# Sheet1.net
KiCad netlist of a schematic drawn in Altium Designer
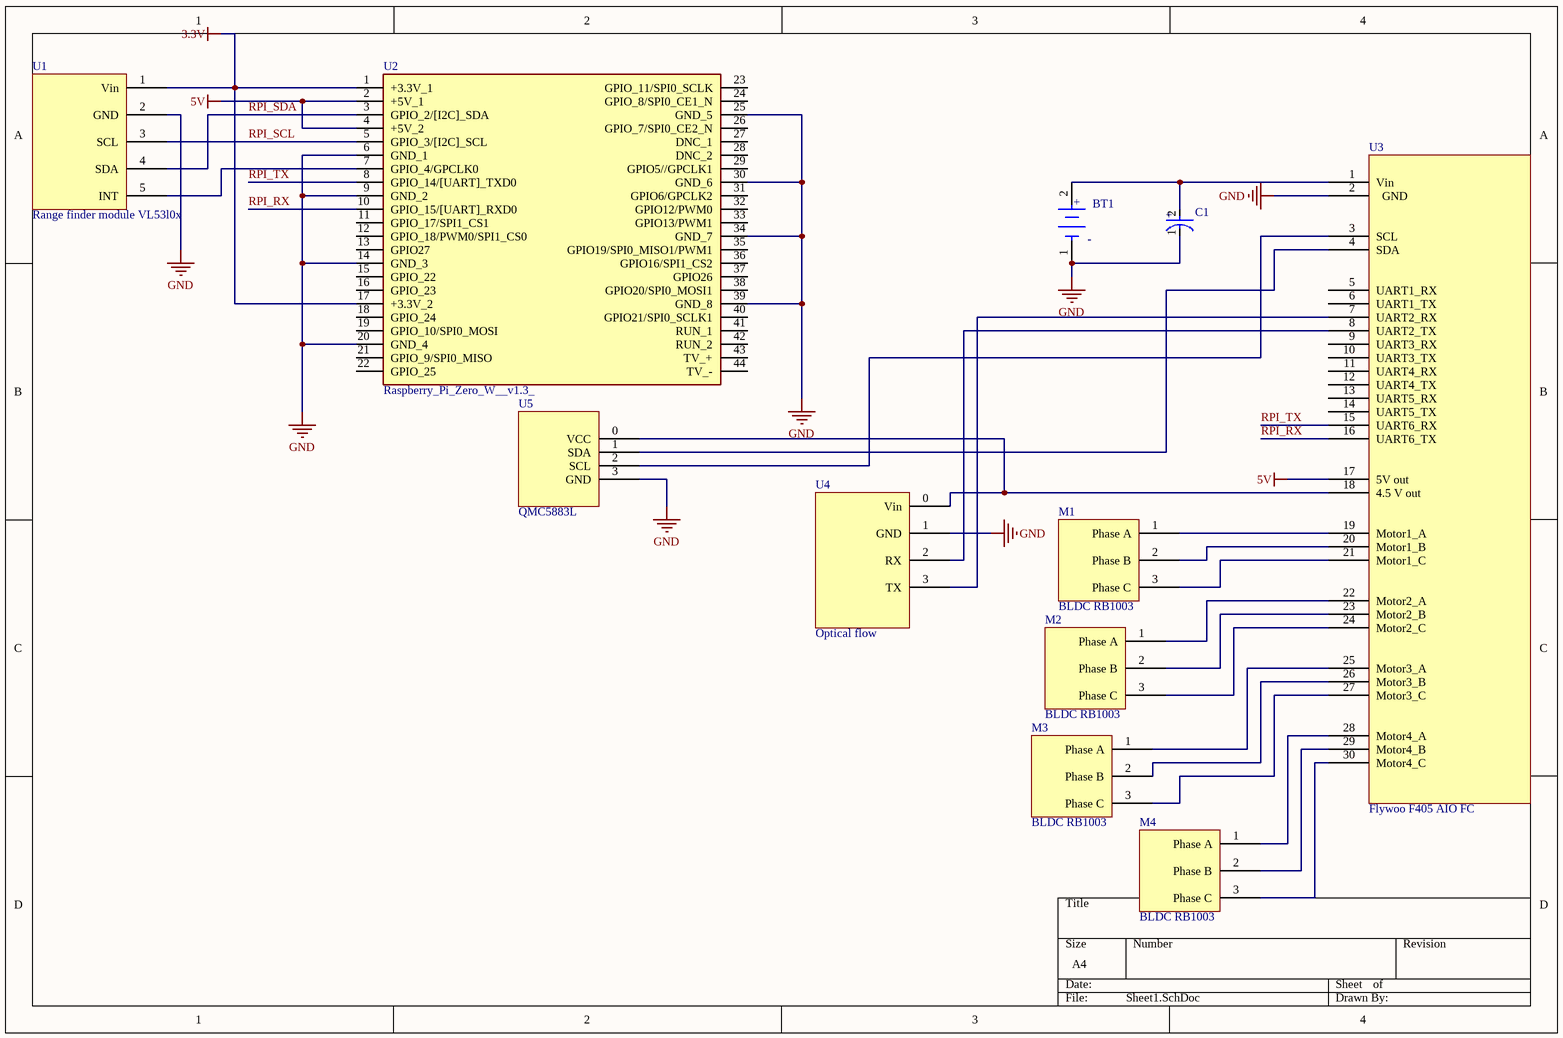
[diagram p0: Sheet1.SchDoc]

(export (version "E")
  (design (tool "Eeschema 10.0.6"))
  (components
    (comp (ref "BT1")
      (value "S8411-45R")
      (footprint "FP-S8411-45R-MFG")
      (description "BATTERY HOLDER COIN 12MM SMD")
      (libsource (lib "Altium Content Vault") (part "60d3b5b901a8747834971d0eb8cf3fd"))
    )
    (comp (ref "C1")
      (value "EEEFK1H101P")
      (footprint "FP-FKF-MFG")
      (description "CAP ALUM 100UF 20% 50V SMD")
      (fields (field (name "VOLTAGE") "50V") (field (name "TOLERANCE") "20%"))
      (libsource (lib "Altium Content Vault") (part "a00bbbee19879c290e62620ae7e47b1"))
    )
    (comp (ref "M1") (value "BLDC RB1003") (libsource (lib "Schlib1") (part "BLDC RB1003")))
    (comp (ref "M2") (value "BLDC RB1003") (libsource (lib "Schlib1") (part "BLDC RB1003")))
    (comp (ref "M3") (value "BLDC RB1003") (libsource (lib "Schlib1") (part "BLDC RB1003")))
    (comp (ref "M4") (value "BLDC RB1003") (libsource (lib "Schlib1") (part "BLDC RB1003")))
    (comp (ref "U1")
      (value "Range finder module VL53l0x")
      (libsource (lib "Schlib1") (part "Range finder module VL53l0x"))
    )
    (comp (ref "U2")
      (value "Raspberry_Pi_Zero_W__v1.3_")
      (footprint "SamacSys:RASPBERRYPIZEROWV13")
      (description "Integrated Circuit")
      (fields (field (name "MANUFACTURER_PART_NUMBER") "Raspberry Pi Zero W (v1.3)"))
      (libsource (lib "*") (part "Raspberry_Pi_Zero_W__v1.3_"))
    )
    (comp (ref "U3") (value "Flywoo F405 AIO FC") (libsource (lib "Schlib1") (part "Flywoo F405 AIO FC")))
    (comp (ref "U4") (value "Optical flow") (libsource (lib "Schlib1") (part "MTF_02 (PMW3901)")))
    (comp (ref "U5") (value "QMC5883L") (libsource (lib "Schlib1") (part "QMC5883L")))
  )
  (nets
    (net (code "1") (name "/RPI_RX") (class "Default")
      (node (ref "U2") (pin "10") (pinfunction "GPIO_15/[UART]_RXD0_10") (pintype "passive"))
      (node (ref "U3") (pin "16") (pinfunction "UART6_TX_16") (pintype "passive"))
    )
    (net (code "2") (name "/RPI_SCL") (class "Default")
      (node (ref "U1") (pin "3") (pinfunction "SCL_3") (pintype "passive"))
      (node (ref "U2") (pin "5") (pinfunction "GPIO_3/[I2C]_SCL_5") (pintype "passive"))
    )
    (net (code "3") (name "/RPI_SDA") (class "Default")
      (node (ref "U1") (pin "4") (pinfunction "SDA_4") (pintype "passive"))
      (node (ref "U2") (pin "3") (pinfunction "GPIO_2/[I2C]_SDA_3") (pintype "passive"))
    )
    (net (code "4") (name "/RPI_TX") (class "Default")
      (node (ref "U2") (pin "8") (pinfunction "GPIO_14/[UART]_TXD0_8") (pintype "passive"))
      (node (ref "U3") (pin "15") (pinfunction "UART6_RX_15") (pintype "passive"))
    )
    (net (code "5") (name "3.3V") (class "Default")
      (node (ref "U1") (pin "1") (pinfunction "Vin_1") (pintype "passive"))
      (node (ref "U2") (pin "1") (pinfunction "+3.3V_1_1") (pintype "passive"))
      (node (ref "U2") (pin "17") (pinfunction "+3.3V_2_17") (pintype "passive"))
    )
    (net (code "6") (name "5V") (class "Default")
      (node (ref "U2") (pin "2") (pinfunction "+5V_1_2") (pintype "passive"))
      (node (ref "U2") (pin "4") (pinfunction "+5V_2_4") (pintype "passive"))
      (node (ref "U3") (pin "17") (pinfunction "5V_out_17") (pintype "passive"))
    )
    (net (code "7") (name "GND") (class "Default")
      (node (ref "BT1") (pin "1") (pinfunction "C_1") (pintype "passive"))
      (node (ref "C1") (pin "1") (pinfunction "C_1") (pintype "passive"))
      (node (ref "U1") (pin "2") (pinfunction "GND_2") (pintype "passive"))
      (node (ref "U2") (pin "14") (pinfunction "GND_3_14") (pintype "passive"))
      (node (ref "U2") (pin "20") (pinfunction "GND_4_20") (pintype "passive"))
      (node (ref "U2") (pin "25") (pinfunction "GND_5_25") (pintype "passive"))
      (node (ref "U2") (pin "30") (pinfunction "GND_6_30") (pintype "passive"))
      (node (ref "U2") (pin "34") (pinfunction "GND_7_34") (pintype "passive"))
      (node (ref "U2") (pin "39") (pinfunction "GND_8_39") (pintype "passive"))
      (node (ref "U2") (pin "6") (pinfunction "GND_1_6") (pintype "passive"))
      (node (ref "U2") (pin "9") (pinfunction "GND_2_9") (pintype "passive"))
      (node (ref "U3") (pin "2") (pinfunction "__GND_2") (pintype "passive"))
      (node (ref "U4") (pin "1") (pinfunction "GND_1") (pintype "passive"))
      (node (ref "U5") (pin "3") (pinfunction "GND_3") (pintype "passive"))
    )
    (net (code "8") (name "Net-(BT1-A)") (class "Default")
      (node (ref "BT1") (pin "2") (pinfunction "A_2") (pintype "passive"))
      (node (ref "C1") (pin "2") (pinfunction "A_2") (pintype "passive"))
      (node (ref "U3") (pin "1") (pinfunction "Vin_1") (pintype "passive"))
    )
    (net (code "9") (name "Net-(M1-Phase_A)") (class "Default")
      (node (ref "M1") (pin "1") (pinfunction "Phase_A_1") (pintype "passive"))
      (node (ref "U3") (pin "19") (pinfunction "Motor1_A_19") (pintype "passive"))
    )
    (net (code "10") (name "Net-(M1-Phase_B)") (class "Default")
      (node (ref "M1") (pin "2") (pinfunction "Phase_B_2") (pintype "passive"))
      (node (ref "U3") (pin "20") (pinfunction "Motor1_B_20") (pintype "passive"))
    )
    (net (code "11") (name "Net-(M1-Phase_C)") (class "Default")
      (node (ref "M1") (pin "3") (pinfunction "Phase_C_3") (pintype "passive"))
      (node (ref "U3") (pin "21") (pinfunction "Motor1_C_21") (pintype "passive"))
    )
    (net (code "12") (name "Net-(M2-Phase_A)") (class "Default")
      (node (ref "M2") (pin "1") (pinfunction "Phase_A_1") (pintype "passive"))
      (node (ref "U3") (pin "22") (pinfunction "Motor2_A_22") (pintype "passive"))
    )
    (net (code "13") (name "Net-(M2-Phase_B)") (class "Default")
      (node (ref "M2") (pin "2") (pinfunction "Phase_B_2") (pintype "passive"))
      (node (ref "U3") (pin "23") (pinfunction "Motor2_B_23") (pintype "passive"))
    )
    (net (code "14") (name "Net-(M2-Phase_C)") (class "Default")
      (node (ref "M2") (pin "3") (pinfunction "Phase_C_3") (pintype "passive"))
      (node (ref "U3") (pin "24") (pinfunction "Motor2_C_24") (pintype "passive"))
    )
    (net (code "15") (name "Net-(M3-Phase_A)") (class "Default")
      (node (ref "M3") (pin "1") (pinfunction "Phase_A_1") (pintype "passive"))
      (node (ref "U3") (pin "25") (pinfunction "Motor3_A_25") (pintype "passive"))
    )
    (net (code "16") (name "Net-(M3-Phase_B)") (class "Default")
      (node (ref "M3") (pin "2") (pinfunction "Phase_B_2") (pintype "passive"))
      (node (ref "U3") (pin "26") (pinfunction "Motor3_B_26") (pintype "passive"))
    )
    (net (code "17") (name "Net-(M3-Phase_C)") (class "Default")
      (node (ref "M3") (pin "3") (pinfunction "Phase_C_3") (pintype "passive"))
      (node (ref "U3") (pin "27") (pinfunction "Motor3_C_27") (pintype "passive"))
    )
    (net (code "18") (name "Net-(M4-Phase_A)") (class "Default")
      (node (ref "M4") (pin "1") (pinfunction "Phase_A_1") (pintype "passive"))
      (node (ref "U3") (pin "28") (pinfunction "Motor4_A_28") (pintype "passive"))
    )
    (net (code "19") (name "Net-(M4-Phase_B)") (class "Default")
      (node (ref "M4") (pin "2") (pinfunction "Phase_B_2") (pintype "passive"))
      (node (ref "U3") (pin "29") (pinfunction "Motor4_B_29") (pintype "passive"))
    )
    (net (code "20") (name "Net-(M4-Phase_C)") (class "Default")
      (node (ref "M4") (pin "3") (pinfunction "Phase_C_3") (pintype "passive"))
      (node (ref "U3") (pin "30") (pinfunction "Motor4_C_30") (pintype "passive"))
    )
    (net (code "21") (name "Net-(U1-INT)") (class "Default")
      (node (ref "U1") (pin "5") (pinfunction "INT_5") (pintype "passive"))
      (node (ref "U2") (pin "7") (pinfunction "GPIO_4/GPCLK0_7") (pintype "passive"))
    )
    (net (code "22") (name "Net-(U3-4.5_V_out)") (class "Default")
      (node (ref "U3") (pin "18") (pinfunction "4.5_V_out_18") (pintype "passive"))
      (node (ref "U4") (pin "0") (pinfunction "Vin_0") (pintype "passive"))
      (node (ref "U5") (pin "0") (pinfunction "VCC_0") (pintype "passive"))
    )
    (net (code "23") (name "Net-(U3-SCL)") (class "Default")
      (node (ref "U3") (pin "3") (pinfunction "SCL_3") (pintype "passive"))
      (node (ref "U5") (pin "2") (pinfunction "SCL_2") (pintype "passive"))
    )
    (net (code "24") (name "Net-(U3-SDA)") (class "Default")
      (node (ref "U3") (pin "4") (pinfunction "SDA_4") (pintype "passive"))
      (node (ref "U5") (pin "1") (pinfunction "SDA_1") (pintype "passive"))
    )
    (net (code "25") (name "Net-(U3-UART2_RX)") (class "Default")
      (node (ref "U3") (pin "7") (pinfunction "UART2_RX_7") (pintype "passive"))
      (node (ref "U4") (pin "3") (pinfunction "TX_3") (pintype "passive"))
    )
    (net (code "26") (name "Net-(U3-UART2_TX)") (class "Default")
      (node (ref "U3") (pin "8") (pinfunction "UART2_TX_8") (pintype "passive"))
      (node (ref "U4") (pin "2") (pinfunction "RX_2") (pintype "passive"))
    )
    (net (code "27") (name "unconnected-(U2-DNC_1-Pad27)") (class "Default")
      (node (ref "U2") (pin "27") (pinfunction "DNC_1_27") (pintype "passive"))
    )
    (net (code "28") (name "unconnected-(U2-DNC_2-Pad28)") (class "Default")
      (node (ref "U2") (pin "28") (pinfunction "DNC_2_28") (pintype "passive"))
    )
    (net (code "29") (name "unconnected-(U2-GPIO5{slash}{slash}GPCLK1-Pad29)") (class "Default")
      (node (ref "U2") (pin "29") (pinfunction "GPIO5//GPCLK1_29") (pintype "passive"))
    )
    (net (code "30") (name "unconnected-(U2-GPIO6{slash}GPCLK2-Pad31)") (class "Default")
      (node (ref "U2") (pin "31") (pinfunction "GPIO6/GPCLK2_31") (pintype "passive"))
    )
    (net (code "31") (name "unconnected-(U2-GPIO12{slash}PWM0-Pad32)") (class "Default")
      (node (ref "U2") (pin "32") (pinfunction "GPIO12/PWM0_32") (pintype "passive"))
    )
    (net (code "32") (name "unconnected-(U2-GPIO13{slash}PWM1-Pad33)") (class "Default")
      (node (ref "U2") (pin "33") (pinfunction "GPIO13/PWM1_33") (pintype "passive"))
    )
    (net (code "33") (name "unconnected-(U2-GPIO16{slash}SPI1_CS2-Pad36)") (class "Default")
      (node (ref "U2") (pin "36") (pinfunction "GPIO16/SPI1_CS2_36") (pintype "passive"))
    )
    (net (code "34") (name "unconnected-(U2-GPIO19{slash}SPI0_MISO1{slash}PWM1-Pad35)") (class "Default")
      (node (ref "U2") (pin "35") (pinfunction "GPIO19/SPI0_MISO1/PWM1_35") (pintype "passive"))
    )
    (net (code "35") (name "unconnected-(U2-GPIO20{slash}SPI0_MOSI1-Pad38)") (class "Default")
      (node (ref "U2") (pin "38") (pinfunction "GPIO20/SPI0_MOSI1_38") (pintype "passive"))
    )
    (net (code "36") (name "unconnected-(U2-GPIO21{slash}SPI0_SCLK1-Pad40)") (class "Default")
      (node (ref "U2") (pin "40") (pinfunction "GPIO21/SPI0_SCLK1_40") (pintype "passive"))
    )
    (net (code "37") (name "unconnected-(U2-GPIO26-Pad37)") (class "Default")
      (node (ref "U2") (pin "37") (pinfunction "GPIO26_37") (pintype "passive"))
    )
    (net (code "38") (name "unconnected-(U2-GPIO27-Pad13)") (class "Default")
      (node (ref "U2") (pin "13") (pinfunction "GPIO27_13") (pintype "passive"))
    )
    (net (code "39") (name "unconnected-(U2-GPIO_7{slash}SPI0_CE2_N-Pad26)") (class "Default")
      (node (ref "U2") (pin "26") (pinfunction "GPIO_7/SPI0_CE2_N_26") (pintype "passive"))
    )
    (net (code "40") (name "unconnected-(U2-GPIO_8{slash}SPI0_CE1_N-Pad24)") (class "Default")
      (node (ref "U2") (pin "24") (pinfunction "GPIO_8/SPI0_CE1_N_24") (pintype "passive"))
    )
    (net (code "41") (name "unconnected-(U2-GPIO_9{slash}SPI0_MISO-Pad21)") (class "Default")
      (node (ref "U2") (pin "21") (pinfunction "GPIO_9/SPI0_MISO_21") (pintype "passive"))
    )
    (net (code "42") (name "unconnected-(U2-GPIO_10{slash}SPI0_MOSI-Pad19)") (class "Default")
      (node (ref "U2") (pin "19") (pinfunction "GPIO_10/SPI0_MOSI_19") (pintype "passive"))
    )
    (net (code "43") (name "unconnected-(U2-GPIO_11{slash}SPI0_SCLK-Pad23)") (class "Default")
      (node (ref "U2") (pin "23") (pinfunction "GPIO_11/SPI0_SCLK_23") (pintype "passive"))
    )
    (net (code "44") (name "unconnected-(U2-GPIO_17{slash}SPI1_CS1-Pad11)") (class "Default")
      (node (ref "U2") (pin "11") (pinfunction "GPIO_17/SPI1_CS1_11") (pintype "passive"))
    )
    (net (code "45") (name "unconnected-(U2-GPIO_18{slash}PWM0{slash}SPI1_CS0-Pad12)") (class "Default")
      (node (ref "U2") (pin "12") (pinfunction "GPIO_18/PWM0/SPI1_CS0_12") (pintype "passive"))
    )
    (net (code "46") (name "unconnected-(U2-GPIO_22-Pad15)") (class "Default")
      (node (ref "U2") (pin "15") (pinfunction "GPIO_22_15") (pintype "passive"))
    )
    (net (code "47") (name "unconnected-(U2-GPIO_23-Pad16)") (class "Default")
      (node (ref "U2") (pin "16") (pinfunction "GPIO_23_16") (pintype "passive"))
    )
    (net (code "48") (name "unconnected-(U2-GPIO_24-Pad18)") (class "Default")
      (node (ref "U2") (pin "18") (pinfunction "GPIO_24_18") (pintype "passive"))
    )
    (net (code "49") (name "unconnected-(U2-GPIO_25-Pad22)") (class "Default")
      (node (ref "U2") (pin "22") (pinfunction "GPIO_25_22") (pintype "passive"))
    )
    (net (code "50") (name "unconnected-(U2-RUN_1-Pad41)") (class "Default")
      (node (ref "U2") (pin "41") (pinfunction "RUN_1_41") (pintype "passive"))
    )
    (net (code "51") (name "unconnected-(U2-RUN_2-Pad42)") (class "Default")
      (node (ref "U2") (pin "42") (pinfunction "RUN_2_42") (pintype "passive"))
    )
    (net (code "52") (name "unconnected-(U2-TV_+-Pad43)") (class "Default")
      (node (ref "U2") (pin "43") (pinfunction "TV_+_43") (pintype "passive"))
    )
    (net (code "53") (name "unconnected-(U2-TV_--Pad44)") (class "Default")
      (node (ref "U2") (pin "44") (pinfunction "TV_-_44") (pintype "passive"))
    )
    (net (code "54") (name "unconnected-(U3-UART1_RX-Pad5)") (class "Default")
      (node (ref "U3") (pin "5") (pinfunction "UART1_RX_5") (pintype "passive"))
    )
    (net (code "55") (name "unconnected-(U3-UART1_TX-Pad6)") (class "Default")
      (node (ref "U3") (pin "6") (pinfunction "UART1_TX_6") (pintype "passive"))
    )
    (net (code "56") (name "unconnected-(U3-UART3_RX-Pad9)") (class "Default")
      (node (ref "U3") (pin "9") (pinfunction "UART3_RX_9") (pintype "passive"))
    )
    (net (code "57") (name "unconnected-(U3-UART3_TX-Pad10)") (class "Default")
      (node (ref "U3") (pin "10") (pinfunction "UART3_TX_10") (pintype "passive"))
    )
    (net (code "58") (name "unconnected-(U3-UART4_RX-Pad11)") (class "Default")
      (node (ref "U3") (pin "11") (pinfunction "UART4_RX_11") (pintype "passive"))
    )
    (net (code "59") (name "unconnected-(U3-UART4_TX-Pad12)") (class "Default")
      (node (ref "U3") (pin "12") (pinfunction "UART4_TX_12") (pintype "passive"))
    )
    (net (code "60") (name "unconnected-(U3-UART5_RX-Pad13)") (class "Default")
      (node (ref "U3") (pin "13") (pinfunction "UART5_RX_13") (pintype "passive"))
    )
    (net (code "61") (name "unconnected-(U3-UART5_TX-Pad14)") (class "Default")
      (node (ref "U3") (pin "14") (pinfunction "UART5_TX_14") (pintype "passive"))
    )
  )
)
